# SCH_Assignment_PCB_2025-04-12.net
KiCad netlist of a schematic drawn in EasyEDA
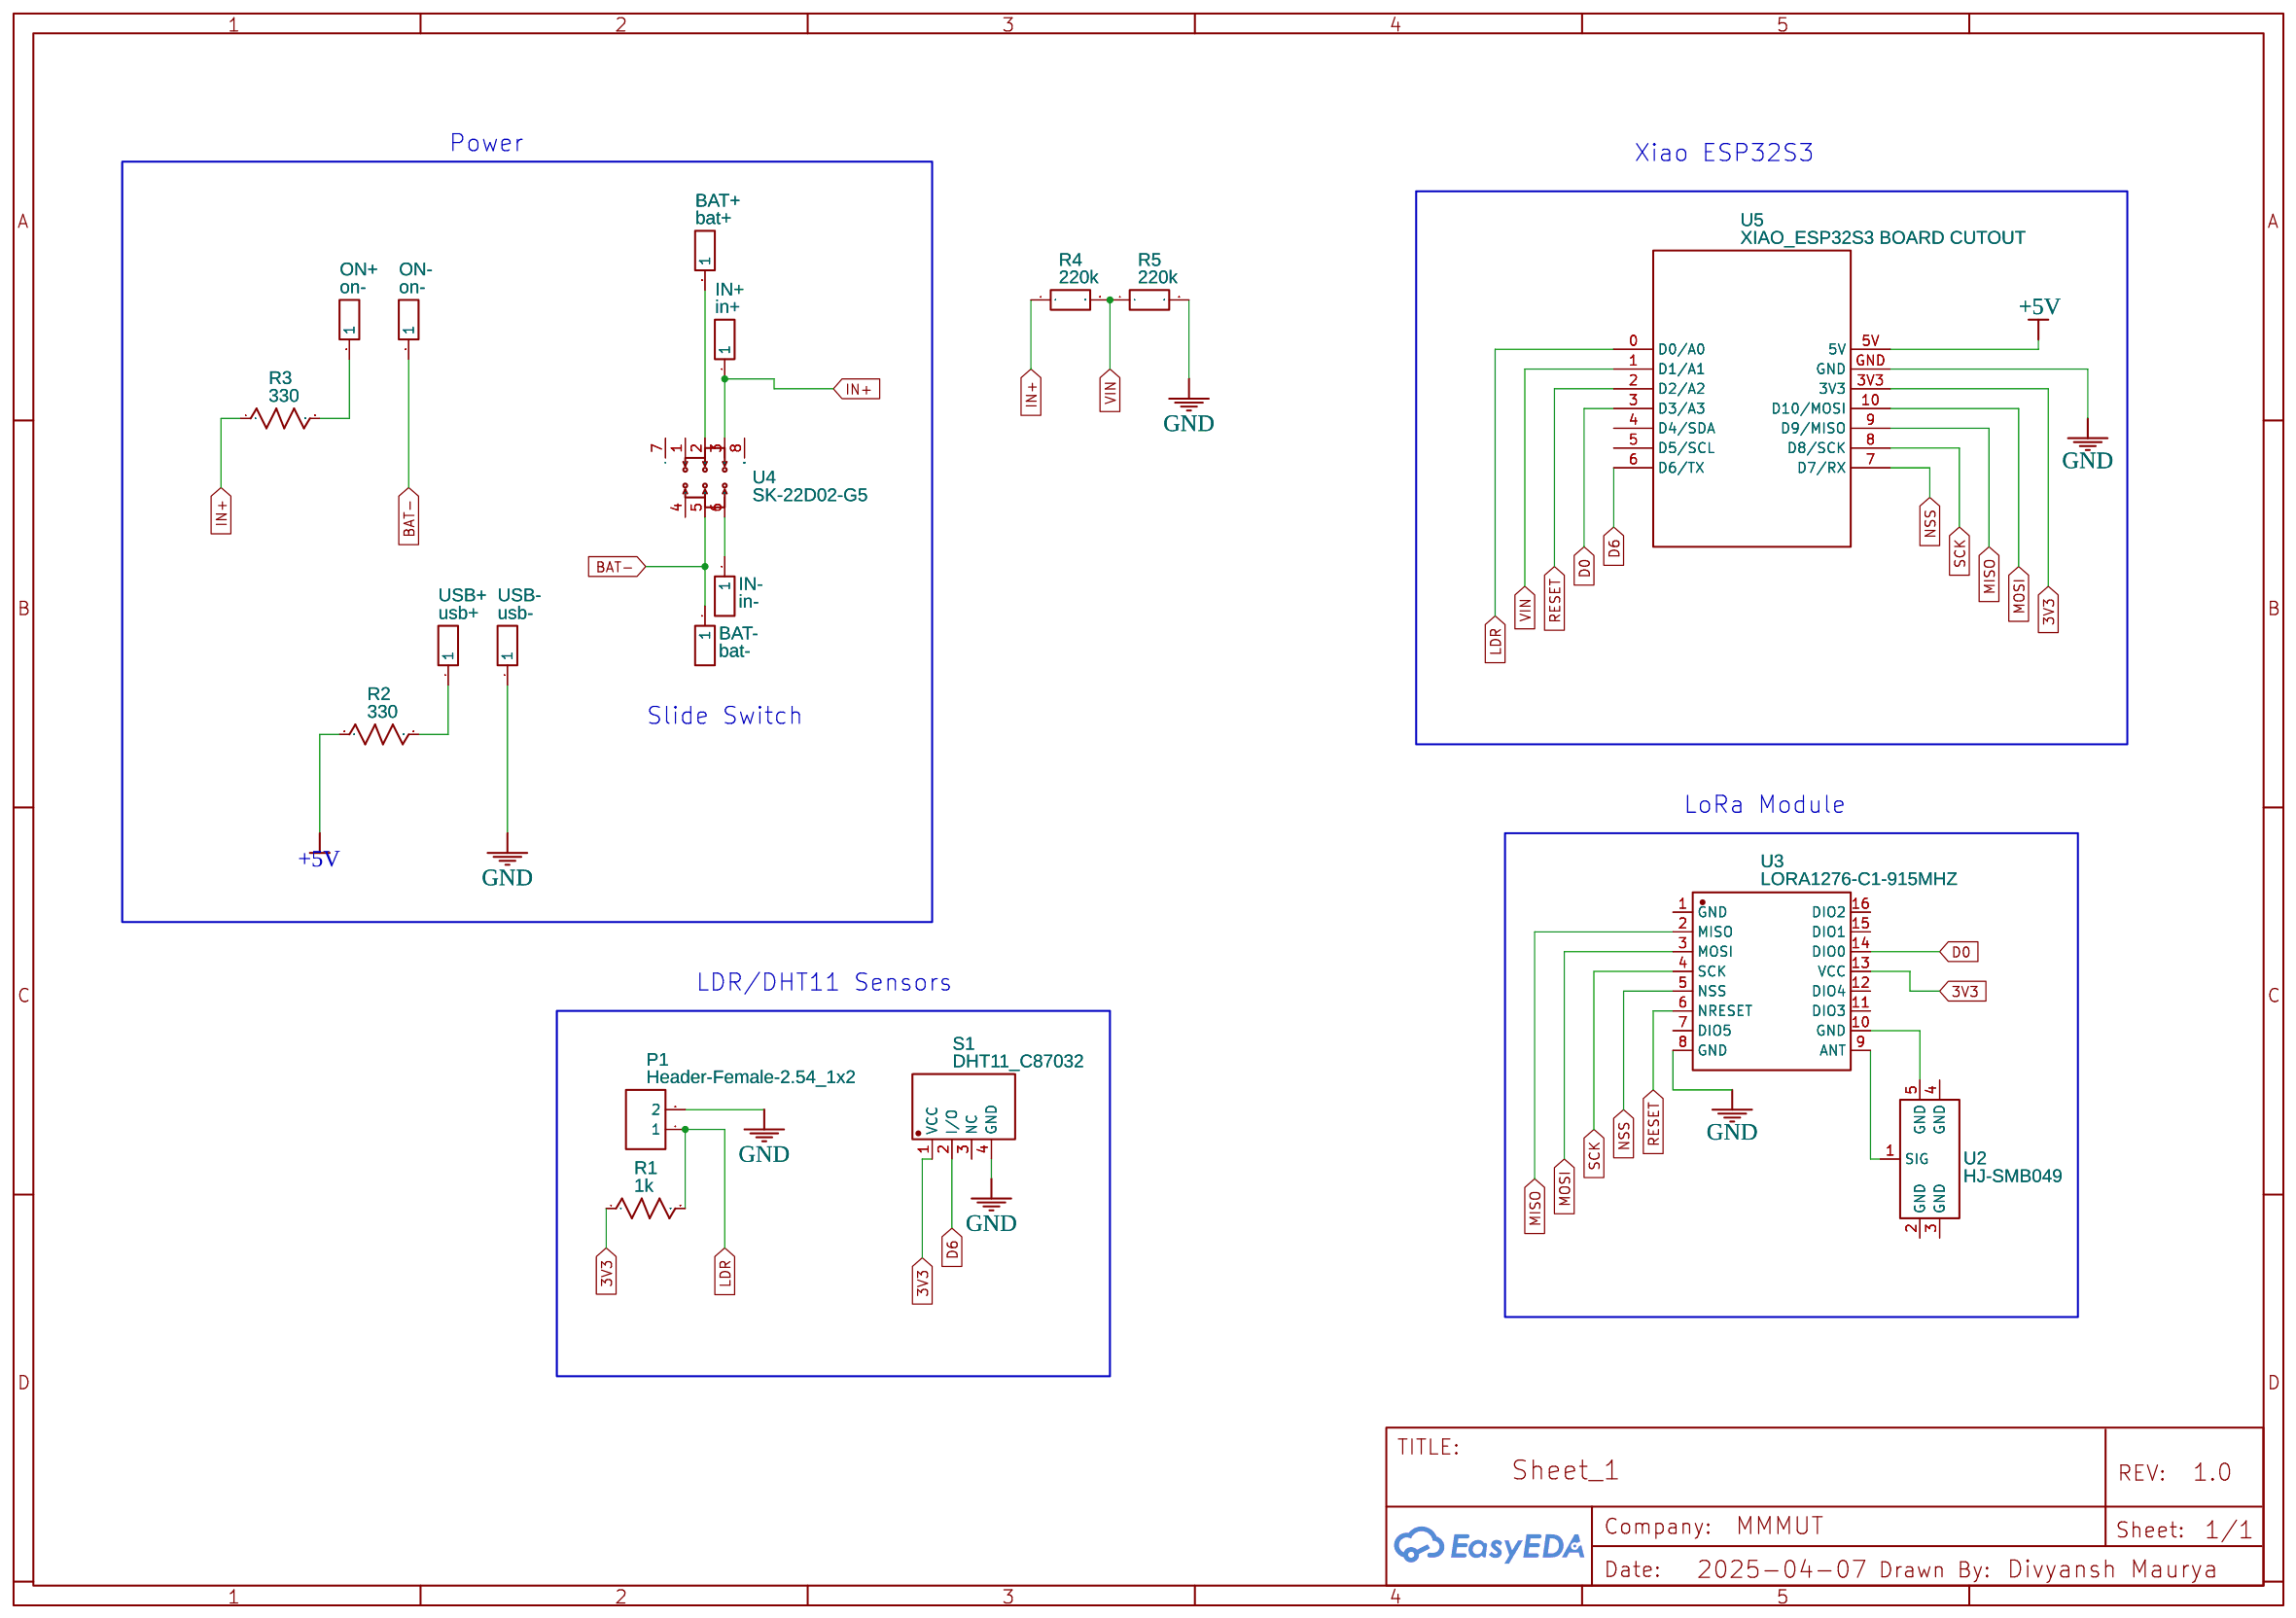
[diagram p0: schematic sheet]

(export (version "E")
  (design (tool "Eeschema 10.0.6"))
  (components
    (comp (ref "BAT+") (value "bat+") (libsource (lib "") (part "HDR-M-2.54_1x1_3")))
    (comp (ref "BAT-") (value "bat-") (libsource (lib "") (part "HDR-M-2.54_1x1_1")))
    (comp (ref "IN+") (value "in+") (libsource (lib "") (part "HDR-M-2.54_1x1_6")))
    (comp (ref "IN-") (value "in-") (libsource (lib "") (part "HDR-M-2.54_1x1_7")))
    (comp (ref "ON+") (value "on-") (libsource (lib "") (part "HDR-M-2.54_1x1_2")))
    (comp (ref "ON-") (value "on-") (libsource (lib "") (part "HDR-M-2.54_1x1_5")))
    (comp (ref "P1")
      (value "Header-Female-2.54_1x2")
      (fields (field (name "Manufacturer Part") "2.54-1*2P母") (field (name "Manufacturer") "BOOMELE(博穆精密)"))
      (libsource (lib "") (part "Header-Female-2.54_1x2"))
    )
    (comp (ref "R1") (value "1k") (libsource (lib "") (part "R_0603_US")))
    (comp (ref "R2") (value "330") (libsource (lib "") (part "R_0603_US")))
    (comp (ref "R3") (value "330") (libsource (lib "") (part "R_0603_US")))
    (comp (ref "R4") (value "220k") (libsource (lib "") (part "R_0603_EU")))
    (comp (ref "R5") (value "220k") (libsource (lib "") (part "R_0603_EU")))
    (comp (ref "S1")
      (value "DHT11_C87032")
      (fields (field (name "Manufacturer Part") "DHT11") (field (name "Manufacturer") "AOSONG"))
      (libsource (lib "") (part "DHT11_C87032"))
    )
    (comp (ref "U2")
      (value "HJ-SMB049")
      (fields (field (name "Manufacturer") "皇捷"))
      (libsource (lib "") (part "HJ-SMB049"))
    )
    (comp (ref "U3")
      (value "LORA1276-C1-915MHZ")
      (fields
        (field (name "Manufacturer Part") "lora1276-C1-915MHz")
        (field (name "Manufacturer") "G-NiceRF(思为无线)")
      )
      (libsource (lib "") (part "LORA1276-C1-915MHZ"))
    )
    (comp (ref "U4")
      (value "SK-22D02-G5")
      (fields (field (name "Manufacturer") "DEALON(德艺隆)"))
      (libsource (lib "") (part "SK-22D02-G5"))
    )
    (comp (ref "U5")
      (value "XIAO_ESP32S3 BOARD CUTOUT")
      (fields (field (name "Manufacturer Part") "XIAO ESP32C3") (field (name "Manufacturer") "SeeedStudio"))
      (libsource (lib "") (part "XIAO_ESP32S3 BOARD CUTOUT"))
    )
    (comp (ref "USB+") (value "usb+") (libsource (lib "") (part "HDR-M-2.54_1x1_4")))
    (comp (ref "USB-") (value "usb-") (libsource (lib "") (part "HDR-M-2.54_1x1")))
  )
  (nets
    (net (code "1") (name "+5V") (class "Default")
      (node (ref "R2") (pin "1") (pinfunction "1_1") (pintype "unspecified"))
      (node (ref "U5") (pin "5V") (pinfunction "5V_5V") (pintype "unspecified"))
    )
    (net (code "2") (name "3V3") (class "Default")
      (node (ref "R1") (pin "1") (pinfunction "1_1") (pintype "unspecified"))
      (node (ref "S1") (pin "1") (pinfunction "VCC_1") (pintype "unspecified"))
      (node (ref "U3") (pin "13") (pinfunction "VCC_13") (pintype "unspecified"))
      (node (ref "U5") (pin "3V3") (pinfunction "3V3_3V3") (pintype "unspecified"))
    )
    (net (code "3") (name "BAT-") (class "Default")
      (node (ref "BAT-") (pin "1") (pinfunction "1_1") (pintype "input"))
      (node (ref "ON-") (pin "1") (pinfunction "1_1") (pintype "input"))
      (node (ref "U4") (pin "5") (pinfunction "5_5") (pintype "unspecified"))
    )
    (net (code "4") (name "D0") (class "Default")
      (node (ref "U3") (pin "14") (pinfunction "DIO0_14") (pintype "unspecified"))
      (node (ref "U5") (pin "3") (pinfunction "D3/A3_3") (pintype "unspecified"))
    )
    (net (code "5") (name "D6") (class "Default")
      (node (ref "S1") (pin "2") (pinfunction "I/O_2") (pintype "unspecified"))
      (node (ref "U5") (pin "6") (pinfunction "D6/TX_6") (pintype "unspecified"))
    )
    (net (code "6") (name "GND") (class "Default")
      (node (ref "P1") (pin "2") (pinfunction "2_2") (pintype "input"))
      (node (ref "R5") (pin "2") (pinfunction "2_2") (pintype "unspecified"))
      (node (ref "S1") (pin "4") (pinfunction "GND_4") (pintype "unspecified"))
      (node (ref "U3") (pin "8") (pinfunction "GND_8") (pintype "unspecified"))
      (node (ref "U5") (pin "GND") (pinfunction "GND_GND") (pintype "unspecified"))
      (node (ref "USB-") (pin "1") (pinfunction "1_1") (pintype "input"))
    )
    (net (code "7") (name "IN+") (class "Default")
      (node (ref "IN+") (pin "1") (pinfunction "1_1") (pintype "input"))
      (node (ref "R3") (pin "1") (pinfunction "1_1") (pintype "unspecified"))
      (node (ref "R4") (pin "1") (pinfunction "1_1") (pintype "unspecified"))
      (node (ref "U4") (pin "3") (pinfunction "3_3") (pintype "unspecified"))
    )
    (net (code "8") (name "LDR") (class "Default")
      (node (ref "P1") (pin "1") (pinfunction "1_1") (pintype "input"))
      (node (ref "R1") (pin "2") (pinfunction "2_2") (pintype "unspecified"))
      (node (ref "U5") (pin "0") (pinfunction "D0/A0_0") (pintype "unspecified"))
    )
    (net (code "9") (name "MISO") (class "Default")
      (node (ref "U3") (pin "2") (pinfunction "MISO_2") (pintype "unspecified"))
      (node (ref "U5") (pin "9") (pinfunction "D9/MISO_9") (pintype "unspecified"))
    )
    (net (code "10") (name "MOSI") (class "Default")
      (node (ref "U3") (pin "3") (pinfunction "MOSI_3") (pintype "unspecified"))
      (node (ref "U5") (pin "10") (pinfunction "D10/MOSI_10") (pintype "unspecified"))
    )
    (net (code "11") (name "NSS") (class "Default")
      (node (ref "U3") (pin "5") (pinfunction "NSS_5") (pintype "unspecified"))
      (node (ref "U5") (pin "7") (pinfunction "D7/RX_7") (pintype "unspecified"))
    )
    (net (code "12") (name "Net-(BAT+-Pad1)") (class "Default")
      (node (ref "BAT+") (pin "1") (pinfunction "1_1") (pintype "input"))
      (node (ref "U4") (pin "2") (pinfunction "2_2") (pintype "unspecified"))
    )
    (net (code "13") (name "Net-(IN--Pad1)") (class "Default")
      (node (ref "IN-") (pin "1") (pinfunction "1_1") (pintype "input"))
      (node (ref "U4") (pin "6") (pinfunction "6_6") (pintype "unspecified"))
    )
    (net (code "14") (name "Net-(ON+-Pad1)") (class "Default")
      (node (ref "ON+") (pin "1") (pinfunction "1_1") (pintype "input"))
      (node (ref "R3") (pin "2") (pinfunction "2_2") (pintype "unspecified"))
    )
    (net (code "15") (name "Net-(R2-Pad2)") (class "Default")
      (node (ref "R2") (pin "2") (pinfunction "2_2") (pintype "unspecified"))
      (node (ref "USB+") (pin "1") (pinfunction "1_1") (pintype "input"))
    )
    (net (code "16") (name "Net-(U2-GND-Pad5)") (class "Default")
      (node (ref "U2") (pin "5") (pinfunction "GND_5") (pintype "unspecified"))
      (node (ref "U3") (pin "10") (pinfunction "GND_10") (pintype "unspecified"))
    )
    (net (code "17") (name "Net-(U2-SIG)") (class "Default")
      (node (ref "U2") (pin "1") (pinfunction "SIG_1") (pintype "unspecified"))
      (node (ref "U3") (pin "9") (pinfunction "ANT_9") (pintype "unspecified"))
    )
    (net (code "18") (name "RESET") (class "Default")
      (node (ref "U3") (pin "6") (pinfunction "NRESET_6") (pintype "unspecified"))
      (node (ref "U5") (pin "2") (pinfunction "D2/A2_2") (pintype "unspecified"))
    )
    (net (code "19") (name "SCK") (class "Default")
      (node (ref "U3") (pin "4") (pinfunction "SCK_4") (pintype "unspecified"))
      (node (ref "U5") (pin "8") (pinfunction "D8/SCK_8") (pintype "unspecified"))
    )
    (net (code "20") (name "VIN") (class "Default")
      (node (ref "R4") (pin "2") (pinfunction "2_2") (pintype "unspecified"))
      (node (ref "R5") (pin "1") (pinfunction "1_1") (pintype "unspecified"))
      (node (ref "U5") (pin "1") (pinfunction "D1/A1_1") (pintype "unspecified"))
    )
    (net (code "21") (name "unconnected-(S1-NC-Pad3)") (class "Default")
      (node (ref "S1") (pin "3") (pinfunction "NC_3") (pintype "unspecified"))
    )
    (net (code "22") (name "unconnected-(U2-GND-Pad2)") (class "Default")
      (node (ref "U2") (pin "2") (pinfunction "GND_2") (pintype "unspecified"))
    )
    (net (code "23") (name "unconnected-(U2-GND-Pad3)") (class "Default")
      (node (ref "U2") (pin "3") (pinfunction "GND_3") (pintype "unspecified"))
    )
    (net (code "24") (name "unconnected-(U2-GND-Pad4)") (class "Default")
      (node (ref "U2") (pin "4") (pinfunction "GND_4") (pintype "unspecified"))
    )
    (net (code "25") (name "unconnected-(U3-DIO1-Pad15)") (class "Default")
      (node (ref "U3") (pin "15") (pinfunction "DIO1_15") (pintype "unspecified"))
    )
    (net (code "26") (name "unconnected-(U3-DIO2-Pad16)") (class "Default")
      (node (ref "U3") (pin "16") (pinfunction "DIO2_16") (pintype "unspecified"))
    )
    (net (code "27") (name "unconnected-(U3-DIO3-Pad11)") (class "Default")
      (node (ref "U3") (pin "11") (pinfunction "DIO3_11") (pintype "unspecified"))
    )
    (net (code "28") (name "unconnected-(U3-DIO4-Pad12)") (class "Default")
      (node (ref "U3") (pin "12") (pinfunction "DIO4_12") (pintype "unspecified"))
    )
    (net (code "29") (name "unconnected-(U3-DIO5-Pad7)") (class "Default")
      (node (ref "U3") (pin "7") (pinfunction "DIO5_7") (pintype "unspecified"))
    )
    (net (code "30") (name "unconnected-(U3-GND-Pad1)") (class "Default")
      (node (ref "U3") (pin "1") (pinfunction "GND_1") (pintype "unspecified"))
    )
    (net (code "31") (name "unconnected-(U4-Pad1)") (class "Default")
      (node (ref "U4") (pin "1") (pinfunction "1_1") (pintype "unspecified"))
    )
    (net (code "32") (name "unconnected-(U4-Pad4)") (class "Default")
      (node (ref "U4") (pin "4") (pinfunction "4_4") (pintype "unspecified"))
    )
    (net (code "33") (name "unconnected-(U4-Pad7)") (class "Default")
      (node (ref "U4") (pin "7") (pinfunction "7_7") (pintype "unspecified"))
    )
    (net (code "34") (name "unconnected-(U4-Pad8)") (class "Default")
      (node (ref "U4") (pin "8") (pinfunction "8_8") (pintype "unspecified"))
    )
    (net (code "35") (name "unconnected-(U5-D4{slash}SDA-Pad4)") (class "Default")
      (node (ref "U5") (pin "4") (pinfunction "D4/SDA_4") (pintype "unspecified"))
    )
    (net (code "36") (name "unconnected-(U5-D5{slash}SCL-Pad5)") (class "Default")
      (node (ref "U5") (pin "5") (pinfunction "D5/SCL_5") (pintype "unspecified"))
    )
  )
)
